# tweeq-BLE4_EBLUE.net
KiCad netlist of a schematic drawn in EAGLE
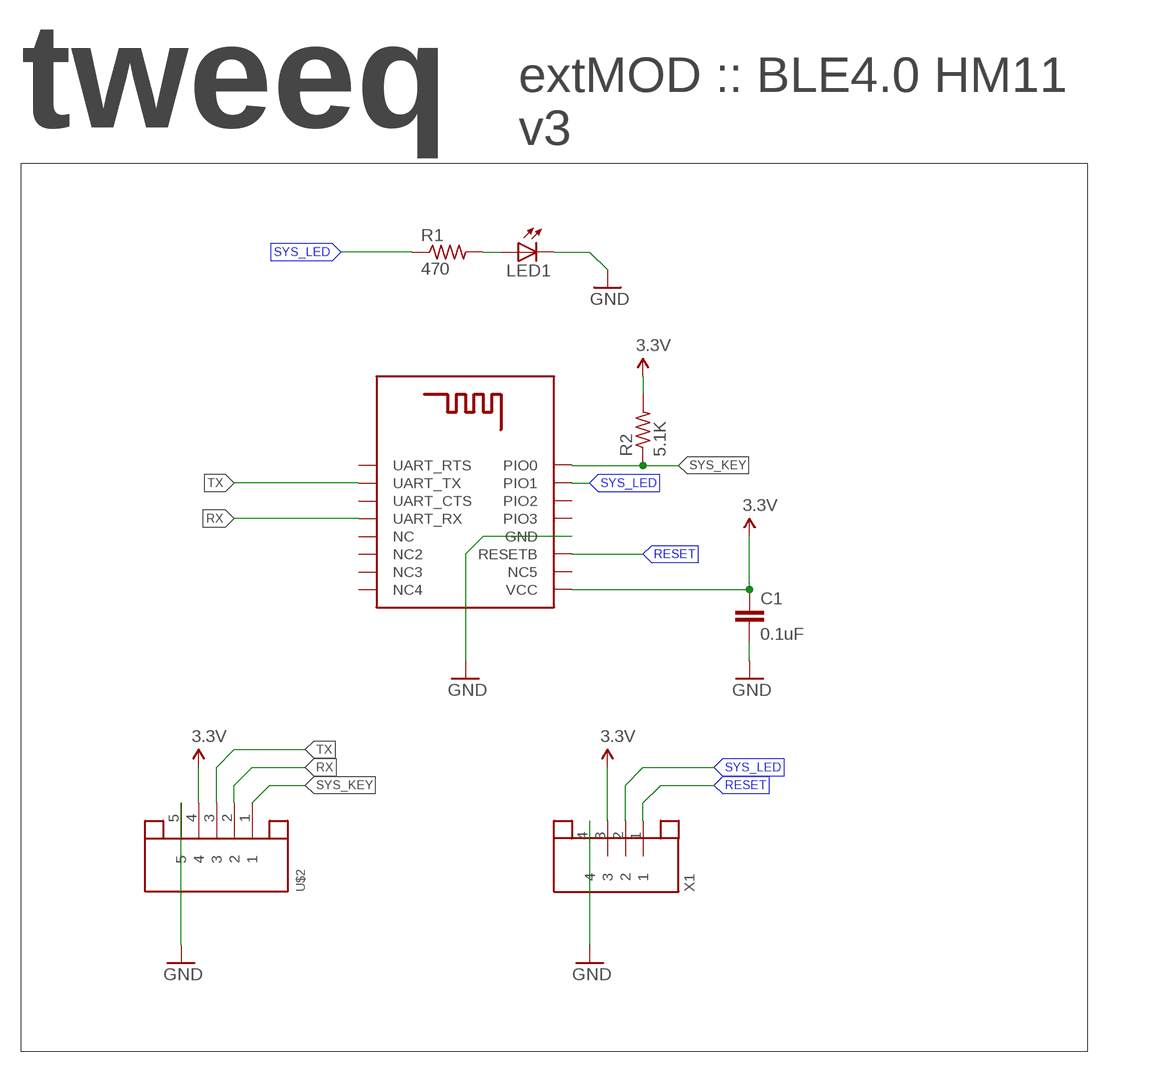
[diagram p0: schematic, sheet 1]

(export (version "E")
  (design (tool "Eeschema 10.0.6"))
  (components
    (comp (ref "C1")
      (value "0.1uF")
      (footprint "eagle-import:C0603K")
      (libsource (lib "eagle-import") (part "C-EUC0603K"))
    )
    (comp (ref "LED1")
      (value "LEDCHIP-LED0805")
      (footprint "eagle-import:CHIP-LED0805")
      (libsource (lib "eagle-import") (part "LEDCHIP-LED0805"))
    )
    (comp (ref "R1")
      (value "470")
      (footprint "eagle-import:R0603")
      (libsource (lib "eagle-import") (part "R-US_R0603"))
    )
    (comp (ref "R2")
      (value "5.1K")
      (footprint "eagle-import:R0603")
      (libsource (lib "eagle-import") (part "R-US_R0603"))
    )
    (comp (ref "U$1")
      (value "EBLUE_BLE4.0_HM11HM11")
      (footprint "eagle-import:BLE4.0_HM11")
      (libsource (lib "eagle-import") (part "EBLUE_BLE4.0_HM11HM11"))
    )
    (comp (ref "U$2")
      (value "JST-5PINEDGE")
      (footprint "eagle-import:SH1.0-5PIN_BLE_EDGE")
      (libsource (lib "eagle-import") (part "JST-5PINEDGE"))
    )
    (comp (ref "X1")
      (value "JST-4PINSH-EDGE")
      (footprint "eagle-import:SH1.0-4PIN_BLE_EDGE")
      (libsource (lib "eagle-import") (part "JST-4PINSH-EDGE"))
    )
  )
  (nets
    (net (code "1") (name "3.3V") (class "Default")
      (node (ref "C1") (pin "1") (pinfunction "1_1") (pintype "passive"))
      (node (ref "R2") (pin "2") (pinfunction "2_2") (pintype "passive"))
      (node (ref "U$1") (pin "P$9") (pinfunction "VCC_P$9") (pintype "power_in"))
      (node (ref "U$2") (pin "4") (pinfunction "4_4") (pintype "bidirectional"))
      (node (ref "X1") (pin "3") (pinfunction "3_3") (pintype "bidirectional"))
    )
    (net (code "2") (name "GND") (class "Default")
      (node (ref "C1") (pin "2") (pinfunction "2_2") (pintype "passive"))
      (node (ref "LED1") (pin "C") (pinfunction "C_C") (pintype "passive"))
      (node (ref "U$1") (pin "P$12") (pinfunction "GND_P$12") (pintype "power_in"))
      (node (ref "U$2") (pin "5") (pinfunction "5_5") (pintype "bidirectional"))
      (node (ref "X1") (pin "4") (pinfunction "4_4") (pintype "bidirectional"))
    )
    (net (code "3") (name "Net-(LED1-PadA)") (class "Default")
      (node (ref "LED1") (pin "A") (pinfunction "A_A") (pintype "passive"))
      (node (ref "R1") (pin "2") (pinfunction "2_2") (pintype "passive"))
    )
    (net (code "4") (name "RESET") (class "Default")
      (node (ref "U$1") (pin "P$11") (pinfunction "RESETB_P$11") (pintype "bidirectional"))
      (node (ref "X1") (pin "1") (pinfunction "1_1") (pintype "bidirectional"))
    )
    (net (code "5") (name "RX") (class "Default")
      (node (ref "U$1") (pin "P$4") (pinfunction "UART_RX_P$4") (pintype "bidirectional"))
      (node (ref "U$2") (pin "2") (pinfunction "2_2") (pintype "bidirectional"))
    )
    (net (code "6") (name "SYS_KEY") (class "Default")
      (node (ref "R2") (pin "1") (pinfunction "1_1") (pintype "passive"))
      (node (ref "U$1") (pin "P$16") (pinfunction "PIO0_P$16") (pintype "bidirectional"))
      (node (ref "U$2") (pin "1") (pinfunction "1_1") (pintype "bidirectional"))
    )
    (net (code "7") (name "SYS_LED") (class "Default")
      (node (ref "R1") (pin "1") (pinfunction "1_1") (pintype "passive"))
      (node (ref "U$1") (pin "P$15") (pinfunction "PIO1_P$15") (pintype "bidirectional"))
      (node (ref "X1") (pin "2") (pinfunction "2_2") (pintype "bidirectional"))
    )
    (net (code "8") (name "TX") (class "Default")
      (node (ref "U$1") (pin "P$2") (pinfunction "UART_TX_P$2") (pintype "bidirectional"))
      (node (ref "U$2") (pin "3") (pinfunction "3_3") (pintype "bidirectional"))
    )
    (net (code "9") (name "unconnected-(U$1-NC-PadP$5)") (class "Default")
      (node (ref "U$1") (pin "P$5") (pinfunction "NC_P$5") (pintype "no_connect"))
    )
    (net (code "10") (name "unconnected-(U$1-NC2-PadP$6)") (class "Default")
      (node (ref "U$1") (pin "P$6") (pinfunction "NC2_P$6") (pintype "no_connect"))
    )
    (net (code "11") (name "unconnected-(U$1-NC3-PadP$7)") (class "Default")
      (node (ref "U$1") (pin "P$7") (pinfunction "NC3_P$7") (pintype "no_connect"))
    )
    (net (code "12") (name "unconnected-(U$1-NC4-PadP$8)") (class "Default")
      (node (ref "U$1") (pin "P$8") (pinfunction "NC4_P$8") (pintype "no_connect"))
    )
    (net (code "13") (name "unconnected-(U$1-NC5-PadP$10)") (class "Default")
      (node (ref "U$1") (pin "P$10") (pinfunction "NC5_P$10") (pintype "no_connect"))
    )
    (net (code "14") (name "unconnected-(U$1-PIO2-PadP$14)") (class "Default")
      (node (ref "U$1") (pin "P$14") (pinfunction "PIO2_P$14") (pintype "bidirectional"))
    )
    (net (code "15") (name "unconnected-(U$1-PIO3-PadP$13)") (class "Default")
      (node (ref "U$1") (pin "P$13") (pinfunction "PIO3_P$13") (pintype "bidirectional"))
    )
    (net (code "16") (name "unconnected-(U$1-UART_CTS-PadP$3)") (class "Default")
      (node (ref "U$1") (pin "P$3") (pinfunction "UART_CTS_P$3") (pintype "bidirectional"))
    )
    (net (code "17") (name "unconnected-(U$1-UART_RTS-PadP$1)") (class "Default")
      (node (ref "U$1") (pin "P$1") (pinfunction "UART_RTS_P$1") (pintype "bidirectional"))
    )
  )
)
